# YOTSUBA_GNSS-receiver_MAX_ver_1_0.net
KiCad netlist of a schematic drawn in EAGLE
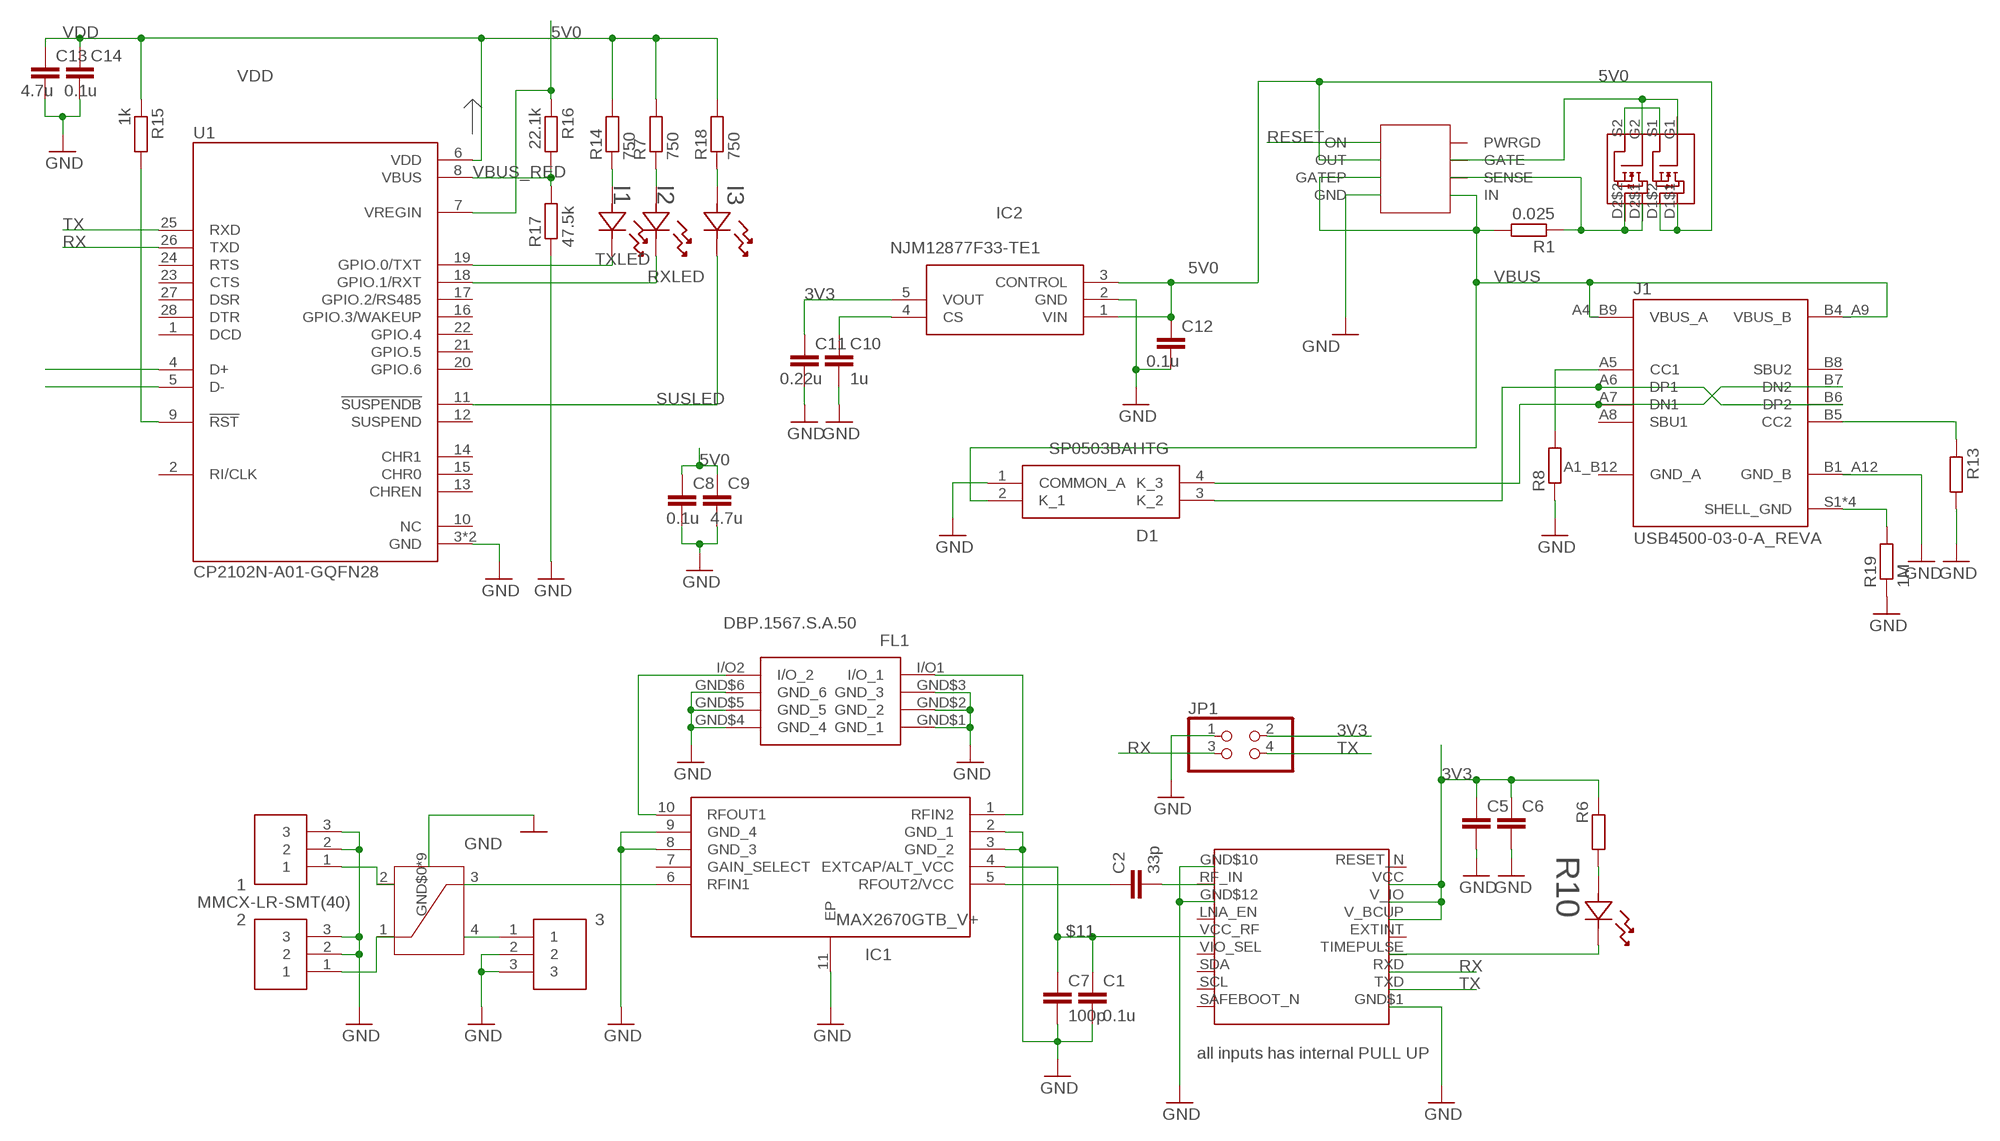
[diagram p0: schematic, sheet 1]

(export (version "E")
  (design (tool "Eeschema 10.0.6"))
  (components
    (comp (ref "1")
      (value "MMCX-LR-SMT(40)")
      (footprint "eagle-import:MMCX-LR-SMT(40)")
      (libsource (lib "eagle-import") (part "MMCX-LR-SMT(40)"))
    )
    (comp (ref "2")
      (value "MMCX-LR-SMT(40)")
      (footprint "eagle-import:MMCX-LR-SMT(40)")
      (libsource (lib "eagle-import") (part "MMCX-LR-SMT(40)"))
    )
    (comp (ref "3")
      (value "MMCX-LR-SMT(40)")
      (footprint "eagle-import:MMCX-LR-SMT(40)")
      (libsource (lib "eagle-import") (part "MMCX-LR-SMT(40)"))
    )
    (comp (ref "C1")
      (value "0.1u")
      (footprint "eagle-import:C1608")
      (libsource (lib "eagle-import") (part "C-EUC1608"))
    )
    (comp (ref "C2")
      (value "33p")
      (footprint "eagle-import:C1608")
      (libsource (lib "eagle-import") (part "C-EUC1608"))
    )
    (comp (ref "C5")
      (value "C-EUC1608")
      (footprint "eagle-import:C1608")
      (libsource (lib "eagle-import") (part "C-EUC1608"))
    )
    (comp (ref "C6")
      (value "C-EUC1608")
      (footprint "eagle-import:C1608")
      (libsource (lib "eagle-import") (part "C-EUC1608"))
    )
    (comp (ref "C7")
      (value "100p")
      (footprint "eagle-import:C1608")
      (libsource (lib "eagle-import") (part "C-EUC1608"))
    )
    (comp (ref "C8")
      (value "0.1u")
      (footprint "eagle-import:C1608")
      (libsource (lib "eagle-import") (part "C-EUC1608"))
    )
    (comp (ref "C9")
      (value "4.7u")
      (footprint "eagle-import:C1608")
      (libsource (lib "eagle-import") (part "C-EUC1608"))
    )
    (comp (ref "C10")
      (value "1u")
      (footprint "eagle-import:C1608")
      (libsource (lib "eagle-import") (part "C-EUC1608"))
    )
    (comp (ref "C11")
      (value "0.22u")
      (footprint "eagle-import:C1608")
      (libsource (lib "eagle-import") (part "C-EUC1608"))
    )
    (comp (ref "C12")
      (value "0.1u")
      (footprint "eagle-import:C1608")
      (libsource (lib "eagle-import") (part "C-EUC1608"))
    )
    (comp (ref "C13")
      (value "4.7u")
      (footprint "eagle-import:C1608")
      (libsource (lib "eagle-import") (part "C-EUC1608"))
    )
    (comp (ref "C14")
      (value "0.1u")
      (footprint "eagle-import:C1608")
      (libsource (lib "eagle-import") (part "C-EUC1608"))
    )
    (comp (ref "D1")
      (value "SP0503BAHTG")
      (footprint "eagle-import:SP0503BAHTG")
      (fields (field (name "MOUSER_PART_NUMBER") "576-SP0503BAHTG"))
      (libsource (lib "eagle-import") (part "SP0503BAHTG"))
    )
    (comp (ref "FL1")
      (value "DBP.1567.S.A.50")
      (footprint "eagle-import:DBP1567SA50")
      (libsource (lib "eagle-import") (part "DBP.1567.S.A.50"))
    )
    (comp (ref "I1")
      (value "SML-E12P8WT86")
      (footprint "eagle-import:LED_SMLD12_ROM")
      (fields (field (name "COPYRIGHT") "Copyright (C) 2023 Ultra Librarian. All rights reserved."))
      (libsource (lib "eagle-import") (part "SML-E12P8WT86"))
    )
    (comp (ref "I2")
      (value "SML-E12P8WT86")
      (footprint "eagle-import:LED_SMLD12_ROM")
      (fields (field (name "COPYRIGHT") "Copyright (C) 2023 Ultra Librarian. All rights reserved."))
      (libsource (lib "eagle-import") (part "SML-E12P8WT86"))
    )
    (comp (ref "I3")
      (value "SML-E12P8WT86")
      (footprint "eagle-import:LED_SMLD12_ROM")
      (fields (field (name "COPYRIGHT") "Copyright (C) 2023 Ultra Librarian. All rights reserved."))
      (libsource (lib "eagle-import") (part "SML-E12P8WT86"))
    )
    (comp (ref "IC1")
      (value "MAX2670GTB_V+")
      (footprint "eagle-import:SON50P300X300X80-11N")
      (fields
        (field (name "MANUFACTURER_PART_NUMBER") "MAX2670GTB/V+")
        (field (name "MOUSER_PART_NUMBER") "700-MAX2670GTB/V+")
      )
      (libsource (lib "eagle-import") (part "MAX2670GTB_V+"))
    )
    (comp (ref "IC2")
      (value "NJM12877F33-TE1")
      (footprint "eagle-import:SOT95P280X120-5N")
      (fields (field (name "MOUSER_PART_NUMBER") "513-NJM12877F33-TE1"))
      (libsource (lib "eagle-import") (part "NJM12877F33-TE1"))
    )
    (comp (ref "J1")
      (value "USB4500-03-0-A_REVA")
      (footprint "eagle-import:GCT_USB4500-03-0-A_REVA")
      (fields
        (field (name "DIGI-KEY_PART_NUMBER") "2073-USB4500-03-0-ATR-ND")
        (field (name "MF") "Global Connector Technology")
        (field (name "MP") "USB4500-03-0-A")
      )
      (libsource (lib "eagle-import") (part "USB4500-03-0-A_REVA"))
    )
    (comp (ref "JP1")
      (value "PINHD-2X2")
      (footprint "eagle-import:2X02")
      (libsource (lib "eagle-import") (part "PINHD-2X2"))
    )
    (comp (ref "R1")
      (value "0.025")
      (footprint "eagle-import:R0603")
      (libsource (lib "eagle-import") (part "R-EU_R0603"))
    )
    (comp (ref "R6")
      (value "R-EU_R0603")
      (footprint "eagle-import:R0603")
      (libsource (lib "eagle-import") (part "R-EU_R0603"))
    )
    (comp (ref "R7")
      (value "750")
      (footprint "eagle-import:R0603")
      (libsource (lib "eagle-import") (part "R-EU_R0603"))
    )
    (comp (ref "R8")
      (value "R-EU_R0603")
      (footprint "eagle-import:R0603")
      (libsource (lib "eagle-import") (part "R-EU_R0603"))
    )
    (comp (ref "R10")
      (value "SML-E12P8WT86")
      (footprint "eagle-import:LED_SMLD12_ROM")
      (fields (field (name "COPYRIGHT") "Copyright (C) 2023 Ultra Librarian. All rights reserved."))
      (libsource (lib "eagle-import") (part "SML-E12P8WT86"))
    )
    (comp (ref "R13")
      (value "R-EU_R0603")
      (footprint "eagle-import:R0603")
      (libsource (lib "eagle-import") (part "R-EU_R0603"))
    )
    (comp (ref "R14")
      (value "750")
      (footprint "eagle-import:R0603")
      (libsource (lib "eagle-import") (part "R-EU_R0603"))
    )
    (comp (ref "R15")
      (value "1k")
      (footprint "eagle-import:R0603")
      (libsource (lib "eagle-import") (part "R-EU_R0603"))
    )
    (comp (ref "R16")
      (value "22.1k")
      (footprint "eagle-import:R0603")
      (libsource (lib "eagle-import") (part "R-EU_R0603"))
    )
    (comp (ref "R17")
      (value "47.5k")
      (footprint "eagle-import:R0603")
      (libsource (lib "eagle-import") (part "R-EU_R0603"))
    )
    (comp (ref "R18")
      (value "750")
      (footprint "eagle-import:R0603")
      (libsource (lib "eagle-import") (part "R-EU_R0603"))
    )
    (comp (ref "R19")
      (value "1M")
      (footprint "eagle-import:R0603")
      (libsource (lib "eagle-import") (part "R-EU_R0603"))
    )
    (comp (ref "U$1")
      (value "MAX_M10S")
      (footprint "eagle-import:MAX-M10S")
      (libsource (lib "eagle-import") (part "MAX_M10S"))
    )
    (comp (ref "U$3")
      (value "HC125.A")
      (footprint "eagle-import:HC125.A")
      (libsource (lib "eagle-import") (part "HC125.A"))
    )
    (comp (ref "U$7")
      (value "DMG6898LSD")
      (footprint "eagle-import:SOIC127P600X150-8N")
      (libsource (lib "eagle-import") (part "DMG6898LSD"))
    )
    (comp (ref "U$8")
      (value "LTC4361")
      (footprint "eagle-import:SOP65P280X100-8N")
      (libsource (lib "eagle-import") (part "LTC4361"))
    )
    (comp (ref "U1")
      (value "CP2102N-A01-GQFN28")
      (footprint "eagle-import:QFN50P500X500X80-29N")
      (fields (field (name "MF") "Silicon Labs"))
      (libsource (lib "eagle-import") (part "CP2102N-A01-GQFN28"))
    )
  )
  (nets
    (net (code "1") (name "/$11") (class "Default")
      (node (ref "C1") (pin "1") (pinfunction "1_1") (pintype "passive"))
      (node (ref "C7") (pin "1") (pinfunction "1_1") (pintype "passive"))
      (node (ref "IC1") (pin "4") (pinfunction "EXTCAP/ALT_VCC_4") (pintype "bidirectional"))
      (node (ref "U$1") (pin "VCC_RF") (pinfunction "VCC_RF_VCC_RF") (pintype "bidirectional"))
    )
    (net (code "2") (name "/3V3") (class "Default")
      (node (ref "C11") (pin "1") (pinfunction "1_1") (pintype "passive"))
      (node (ref "C5") (pin "1") (pinfunction "1_1") (pintype "passive"))
      (node (ref "C6") (pin "1") (pinfunction "1_1") (pintype "passive"))
      (node (ref "IC2") (pin "5") (pinfunction "VOUT_5") (pintype "bidirectional"))
      (node (ref "JP1") (pin "2") (pinfunction "2_2") (pintype "passive"))
      (node (ref "R6") (pin "2") (pinfunction "2_2") (pintype "passive"))
      (node (ref "U$1") (pin "VCC") (pinfunction "VCC_VCC") (pintype "bidirectional"))
      (node (ref "U$1") (pin "V_BCUP") (pinfunction "V_BCKP_V_BCUP") (pintype "bidirectional"))
      (node (ref "U$1") (pin "V_IO") (pinfunction "V_IO_V_IO") (pintype "bidirectional"))
    )
    (net (code "3") (name "/5V0") (class "Default")
      (node (ref "C12") (pin "1") (pinfunction "1_1") (pintype "passive"))
      (node (ref "C8") (pin "1") (pinfunction "1_1") (pintype "passive"))
      (node (ref "C9") (pin "1") (pinfunction "1_1") (pintype "passive"))
      (node (ref "IC2") (pin "1") (pinfunction "VIN_1") (pintype "bidirectional"))
      (node (ref "IC2") (pin "3") (pinfunction "CONTROL_3") (pintype "bidirectional"))
      (node (ref "R16") (pin "1") (pinfunction "1_1") (pintype "passive"))
      (node (ref "U$7") (pin "D1$1") (pinfunction "D1$1_D1$1") (pintype "bidirectional"))
      (node (ref "U$7") (pin "D1$2") (pinfunction "D1$2_D1$2") (pintype "bidirectional"))
      (node (ref "U$8") (pin "OUT") (pinfunction "OUT_OUT") (pintype "bidirectional"))
      (node (ref "U1") (pin "7") (pinfunction "VREGIN_7") (pintype "power_in"))
    )
    (net (code "4") (name "/D+") (class "Default")
      (node (ref "D1") (pin "3") (pinfunction "K_2_3") (pintype "bidirectional"))
      (node (ref "J1") (pin "A6") (pinfunction "DP1_A6") (pintype "bidirectional"))
      (node (ref "J1") (pin "B6") (pinfunction "DP2_B6") (pintype "bidirectional"))
      (node (ref "U1") (pin "4") (pinfunction "D+_4") (pintype "bidirectional"))
    )
    (net (code "5") (name "/D-") (class "Default")
      (node (ref "D1") (pin "4") (pinfunction "K_3_4") (pintype "bidirectional"))
      (node (ref "J1") (pin "A7") (pinfunction "DN1_A7") (pintype "bidirectional"))
      (node (ref "J1") (pin "B7") (pinfunction "DN2_B7") (pintype "bidirectional"))
      (node (ref "U1") (pin "5") (pinfunction "D-_5") (pintype "bidirectional"))
    )
    (net (code "6") (name "/GND_A") (class "Default")
      (node (ref "J1") (pin "A1_B12") (pinfunction "GND_A_A1_B12") (pintype "power_in"))
    )
    (net (code "7") (name "/RESET") (class "Default")
      (node (ref "U$8") (pin "ON") (pinfunction "ON_ON") (pintype "bidirectional"))
    )
    (net (code "8") (name "/RX") (class "Default")
      (node (ref "JP1") (pin "3") (pinfunction "3_3") (pintype "passive"))
      (node (ref "U$1") (pin "RXD") (pinfunction "RXD_RXD") (pintype "bidirectional"))
      (node (ref "U1") (pin "26") (pinfunction "TXD_26") (pintype "output"))
    )
    (net (code "9") (name "/RXLED") (class "Default")
      (node (ref "I2") (pin "1") (pinfunction "1_1") (pintype "passive"))
      (node (ref "U1") (pin "18") (pinfunction "GPIO.1/RXT_18") (pintype "bidirectional"))
    )
    (net (code "10") (name "/SUSLED") (class "Default")
      (node (ref "I3") (pin "1") (pinfunction "1_1") (pintype "passive"))
      (node (ref "U1") (pin "11") (pinfunction "~{SUSPENDB}_11") (pintype "output"))
    )
    (net (code "11") (name "/TX") (class "Default")
      (node (ref "JP1") (pin "4") (pinfunction "4_4") (pintype "passive"))
      (node (ref "U$1") (pin "TXD") (pinfunction "TXD_TXD") (pintype "bidirectional"))
      (node (ref "U1") (pin "25") (pinfunction "RXD_25") (pintype "input"))
    )
    (net (code "12") (name "/TXLED") (class "Default")
      (node (ref "I1") (pin "1") (pinfunction "1_1") (pintype "passive"))
      (node (ref "U1") (pin "19") (pinfunction "GPIO.0/TXT_19") (pintype "bidirectional"))
    )
    (net (code "13") (name "/VBUS") (class "Default")
      (node (ref "D1") (pin "2") (pinfunction "K_1_2") (pintype "bidirectional"))
      (node (ref "J1") (pin "A4_B9") (pinfunction "VBUS_A_A4_B9") (pintype "power_in"))
      (node (ref "J1") (pin "B4_A9") (pinfunction "VBUS_B_B4_A9") (pintype "power_in"))
      (node (ref "R1") (pin "2") (pinfunction "2_2") (pintype "passive"))
      (node (ref "U$8") (pin "GATEP") (pinfunction "GATEP_GATEP") (pintype "bidirectional"))
      (node (ref "U$8") (pin "IN") (pinfunction "IN_IN") (pintype "bidirectional"))
    )
    (net (code "14") (name "/VBUS_RED") (class "Default")
      (node (ref "R16") (pin "2") (pinfunction "2_2") (pintype "passive"))
      (node (ref "R17") (pin "2") (pinfunction "2_2") (pintype "passive"))
      (node (ref "U1") (pin "8") (pinfunction "VBUS_8") (pintype "power_in"))
    )
    (net (code "15") (name "/VDD") (class "Default")
      (node (ref "C13") (pin "1") (pinfunction "1_1") (pintype "passive"))
      (node (ref "C14") (pin "1") (pinfunction "1_1") (pintype "passive"))
      (node (ref "R14") (pin "2") (pinfunction "2_2") (pintype "passive"))
      (node (ref "R15") (pin "1") (pinfunction "1_1") (pintype "passive"))
      (node (ref "R18") (pin "2") (pinfunction "2_2") (pintype "passive"))
      (node (ref "R7") (pin "2") (pinfunction "2_2") (pintype "passive"))
      (node (ref "U1") (pin "6") (pinfunction "VDD_6") (pintype "power_in"))
    )
    (net (code "16") (name "GND") (class "Default")
      (node (ref "1") (pin "2") (pinfunction "2_2") (pintype "bidirectional"))
      (node (ref "1") (pin "3") (pinfunction "3_3") (pintype "bidirectional"))
      (node (ref "2") (pin "2") (pinfunction "2_2") (pintype "bidirectional"))
      (node (ref "2") (pin "3") (pinfunction "3_3") (pintype "bidirectional"))
      (node (ref "3") (pin "2") (pinfunction "2_2") (pintype "bidirectional"))
      (node (ref "3") (pin "3") (pinfunction "3_3") (pintype "bidirectional"))
      (node (ref "C1") (pin "2") (pinfunction "2_2") (pintype "passive"))
      (node (ref "C10") (pin "2") (pinfunction "2_2") (pintype "passive"))
      (node (ref "C11") (pin "2") (pinfunction "2_2") (pintype "passive"))
      (node (ref "C12") (pin "2") (pinfunction "2_2") (pintype "passive"))
      (node (ref "C13") (pin "2") (pinfunction "2_2") (pintype "passive"))
      (node (ref "C14") (pin "2") (pinfunction "2_2") (pintype "passive"))
      (node (ref "C5") (pin "2") (pinfunction "2_2") (pintype "passive"))
      (node (ref "C6") (pin "2") (pinfunction "2_2") (pintype "passive"))
      (node (ref "C7") (pin "2") (pinfunction "2_2") (pintype "passive"))
      (node (ref "C8") (pin "2") (pinfunction "2_2") (pintype "passive"))
      (node (ref "C9") (pin "2") (pinfunction "2_2") (pintype "passive"))
      (node (ref "D1") (pin "1") (pinfunction "COMMON_A_1") (pintype "bidirectional"))
      (node (ref "FL1") (pin "GND$1") (pinfunction "GND_1_GND$1") (pintype "bidirectional"))
      (node (ref "FL1") (pin "GND$2") (pinfunction "GND_2_GND$2") (pintype "bidirectional"))
      (node (ref "FL1") (pin "GND$3") (pinfunction "GND_3_GND$3") (pintype "bidirectional"))
      (node (ref "FL1") (pin "GND$4") (pinfunction "GND_4_GND$4") (pintype "bidirectional"))
      (node (ref "FL1") (pin "GND$5") (pinfunction "GND_5_GND$5") (pintype "bidirectional"))
      (node (ref "FL1") (pin "GND$6") (pinfunction "GND_6_GND$6") (pintype "bidirectional"))
      (node (ref "IC1") (pin "11") (pinfunction "EP_11") (pintype "bidirectional"))
      (node (ref "IC1") (pin "2") (pinfunction "GND_1_2") (pintype "bidirectional"))
      (node (ref "IC1") (pin "3") (pinfunction "GND_2_3") (pintype "bidirectional"))
      (node (ref "IC1") (pin "8") (pinfunction "GND_3_8") (pintype "bidirectional"))
      (node (ref "IC1") (pin "9") (pinfunction "GND_4_9") (pintype "bidirectional"))
      (node (ref "IC2") (pin "2") (pinfunction "GND_2") (pintype "bidirectional"))
      (node (ref "J1") (pin "B1_A12") (pinfunction "GND_B_B1_A12") (pintype "power_in"))
      (node (ref "JP1") (pin "1") (pinfunction "1_1") (pintype "passive"))
      (node (ref "R13") (pin "2") (pinfunction "2_2") (pintype "passive"))
      (node (ref "R17") (pin "1") (pinfunction "1_1") (pintype "passive"))
      (node (ref "R19") (pin "1") (pinfunction "1_1") (pintype "passive"))
      (node (ref "R8") (pin "1") (pinfunction "1_1") (pintype "passive"))
      (node (ref "U$1") (pin "GND$1") (pinfunction "GND$1_GND$1") (pintype "bidirectional"))
      (node (ref "U$1") (pin "GND$10") (pinfunction "GND$10_GND$10") (pintype "bidirectional"))
      (node (ref "U$1") (pin "GND$12") (pinfunction "GND$12_GND$12") (pintype "bidirectional"))
      (node (ref "U$3") (pin "GND$0") (pinfunction "GND_GND$0") (pintype "bidirectional"))
      (node (ref "U$3") (pin "GND$1") (pinfunction "GND_GND$1") (pintype "bidirectional"))
      (node (ref "U$3") (pin "GND$2") (pinfunction "GND_GND$2") (pintype "bidirectional"))
      (node (ref "U$3") (pin "GND$3") (pinfunction "GND_GND$3") (pintype "bidirectional"))
      (node (ref "U$3") (pin "GND$4") (pinfunction "GND_GND$4") (pintype "bidirectional"))
      (node (ref "U$3") (pin "GND$5") (pinfunction "GND_GND$5") (pintype "bidirectional"))
      (node (ref "U$3") (pin "GND$6") (pinfunction "GND_GND$6") (pintype "bidirectional"))
      (node (ref "U$3") (pin "GND$7") (pinfunction "GND_GND$7") (pintype "bidirectional"))
      (node (ref "U$3") (pin "GND$8") (pinfunction "GND_GND$8") (pintype "bidirectional"))
      (node (ref "U$8") (pin "GND") (pinfunction "GND_GND") (pintype "bidirectional"))
      (node (ref "U1") (pin "29") (pinfunction "GND_29") (pintype "power_in"))
      (node (ref "U1") (pin "3") (pinfunction "GND_3") (pintype "power_in"))
    )
    (net (code "17") (name "Net-(1-Pad1)") (class "Default")
      (node (ref "1") (pin "1") (pinfunction "1_1") (pintype "bidirectional"))
      (node (ref "U$3") (pin "2") (pinfunction "2_2") (pintype "bidirectional"))
    )
    (net (code "18") (name "Net-(2-Pad1)") (class "Default")
      (node (ref "2") (pin "1") (pinfunction "1_1") (pintype "bidirectional"))
      (node (ref "U$3") (pin "1") (pinfunction "1_1") (pintype "bidirectional"))
    )
    (net (code "19") (name "Net-(3-Pad1)") (class "Default")
      (node (ref "3") (pin "1") (pinfunction "1_1") (pintype "bidirectional"))
      (node (ref "U$3") (pin "4") (pinfunction "4_4") (pintype "bidirectional"))
    )
    (net (code "20") (name "Net-(C2-Pad2)") (class "Default")
      (node (ref "C2") (pin "2") (pinfunction "2_2") (pintype "passive"))
      (node (ref "U$1") (pin "RF_IN") (pinfunction "RF_IN_RF_IN") (pintype "bidirectional"))
    )
    (net (code "21") (name "Net-(FL1-I{slash}O_1)") (class "Default")
      (node (ref "FL1") (pin "I/O1") (pinfunction "I/O_1_I/O1") (pintype "bidirectional"))
      (node (ref "IC1") (pin "1") (pinfunction "RFIN2_1") (pintype "bidirectional"))
    )
    (net (code "22") (name "Net-(FL1-I{slash}O_2)") (class "Default")
      (node (ref "FL1") (pin "I/O2") (pinfunction "I/O_2_I/O2") (pintype "bidirectional"))
      (node (ref "IC1") (pin "10") (pinfunction "RFOUT1_10") (pintype "bidirectional"))
    )
    (net (code "23") (name "Net-(I1-Pad2)") (class "Default")
      (node (ref "I1") (pin "2") (pinfunction "2_2") (pintype "passive"))
      (node (ref "R14") (pin "1") (pinfunction "1_1") (pintype "passive"))
    )
    (net (code "24") (name "Net-(I2-Pad2)") (class "Default")
      (node (ref "I2") (pin "2") (pinfunction "2_2") (pintype "passive"))
      (node (ref "R7") (pin "1") (pinfunction "1_1") (pintype "passive"))
    )
    (net (code "25") (name "Net-(I3-Pad2)") (class "Default")
      (node (ref "I3") (pin "2") (pinfunction "2_2") (pintype "passive"))
      (node (ref "R18") (pin "1") (pinfunction "1_1") (pintype "passive"))
    )
    (net (code "26") (name "Net-(IC1-RFIN1)") (class "Default")
      (node (ref "IC1") (pin "6") (pinfunction "RFIN1_6") (pintype "bidirectional"))
      (node (ref "U$3") (pin "3") (pinfunction "3_3") (pintype "bidirectional"))
    )
    (net (code "27") (name "Net-(IC1-RFOUT2{slash}VCC)") (class "Default")
      (node (ref "C2") (pin "1") (pinfunction "1_1") (pintype "passive"))
      (node (ref "IC1") (pin "5") (pinfunction "RFOUT2/VCC_5") (pintype "bidirectional"))
    )
    (net (code "28") (name "Net-(IC2-CS)") (class "Default")
      (node (ref "C10") (pin "1") (pinfunction "1_1") (pintype "passive"))
      (node (ref "IC2") (pin "4") (pinfunction "CS_4") (pintype "bidirectional"))
    )
    (net (code "29") (name "Net-(J1-CC1)") (class "Default")
      (node (ref "J1") (pin "A5") (pinfunction "CC1_A5") (pintype "bidirectional"))
      (node (ref "R8") (pin "2") (pinfunction "2_2") (pintype "passive"))
    )
    (net (code "30") (name "Net-(J1-CC2)") (class "Default")
      (node (ref "J1") (pin "B5") (pinfunction "CC2_B5") (pintype "bidirectional"))
      (node (ref "R13") (pin "1") (pinfunction "1_1") (pintype "passive"))
    )
    (net (code "31") (name "Net-(J1-SHELL_GND-PadS1)") (class "Default")
      (node (ref "J1") (pin "S1") (pinfunction "SHELL_GND_S1") (pintype "power_in"))
      (node (ref "J1") (pin "S2") (pinfunction "SHELL_GND_S2") (pintype "power_in"))
      (node (ref "J1") (pin "S3") (pinfunction "SHELL_GND_S3") (pintype "power_in"))
      (node (ref "J1") (pin "S4") (pinfunction "SHELL_GND_S4") (pintype "power_in"))
      (node (ref "R19") (pin "2") (pinfunction "2_2") (pintype "passive"))
    )
    (net (code "32") (name "Net-(R1-Pad1)") (class "Default")
      (node (ref "R1") (pin "1") (pinfunction "1_1") (pintype "passive"))
      (node (ref "U$7") (pin "D2$1") (pinfunction "D2$1_D2$1") (pintype "bidirectional"))
      (node (ref "U$7") (pin "D2$2") (pinfunction "D2$2_D2$2") (pintype "bidirectional"))
      (node (ref "U$8") (pin "SENSE") (pinfunction "SENSE_SENSE") (pintype "bidirectional"))
    )
    (net (code "33") (name "Net-(R10-Pad1)") (class "Default")
      (node (ref "R10") (pin "1") (pinfunction "1_1") (pintype "passive"))
      (node (ref "U$1") (pin "TIMEPULSE") (pinfunction "TIMEPULSE_TIMEPULSE") (pintype "bidirectional"))
    )
    (net (code "34") (name "Net-(R10-Pad2)") (class "Default")
      (node (ref "R10") (pin "2") (pinfunction "2_2") (pintype "passive"))
      (node (ref "R6") (pin "1") (pinfunction "1_1") (pintype "passive"))
    )
    (net (code "35") (name "Net-(U$7-PadG1)") (class "Default")
      (node (ref "U$7") (pin "G1") (pinfunction "G1_G1") (pintype "bidirectional"))
      (node (ref "U$7") (pin "G2") (pinfunction "G2_G2") (pintype "bidirectional"))
      (node (ref "U$8") (pin "GATE") (pinfunction "GATE_GATE") (pintype "bidirectional"))
    )
    (net (code "36") (name "Net-(U$7-PadS1)") (class "Default")
      (node (ref "U$7") (pin "S1") (pinfunction "S1_S1") (pintype "bidirectional"))
      (node (ref "U$7") (pin "S2") (pinfunction "S2_S2") (pintype "bidirectional"))
    )
    (net (code "37") (name "Net-(U1-~{RST})") (class "Default")
      (node (ref "R15") (pin "2") (pinfunction "2_2") (pintype "passive"))
      (node (ref "U1") (pin "9") (pinfunction "~{RST}_9") (pintype "input"))
    )
    (net (code "38") (name "unconnected-(IC1-GAIN_SELECT-Pad7)") (class "Default")
      (node (ref "IC1") (pin "7") (pinfunction "GAIN_SELECT_7") (pintype "bidirectional"))
    )
    (net (code "39") (name "unconnected-(J1-SBU1-PadA8)") (class "Default")
      (node (ref "J1") (pin "A8") (pinfunction "SBU1_A8") (pintype "bidirectional"))
    )
    (net (code "40") (name "unconnected-(J1-SBU2-PadB8)") (class "Default")
      (node (ref "J1") (pin "B8") (pinfunction "SBU2_B8") (pintype "bidirectional"))
    )
    (net (code "41") (name "unconnected-(U$1-PadEXTINT)") (class "Default")
      (node (ref "U$1") (pin "EXTINT") (pinfunction "EXTINT_EXTINT") (pintype "bidirectional"))
    )
    (net (code "42") (name "unconnected-(U$1-PadLNA_EN)") (class "Default")
      (node (ref "U$1") (pin "LNA_EN") (pinfunction "LNA_EN_LNA_EN") (pintype "bidirectional"))
    )
    (net (code "43") (name "unconnected-(U$1-PadRESET_N)") (class "Default")
      (node (ref "U$1") (pin "RESET_N") (pinfunction "RESET_N_RESET_N") (pintype "bidirectional"))
    )
    (net (code "44") (name "unconnected-(U$1-PadSAFEBOOT_N)") (class "Default")
      (node (ref "U$1") (pin "SAFEBOOT_N") (pinfunction "SAFEBOOT_N_SAFEBOOT_N") (pintype "bidirectional"))
    )
    (net (code "45") (name "unconnected-(U$1-PadSCL)") (class "Default")
      (node (ref "U$1") (pin "SCL") (pinfunction "SCL_SCL") (pintype "bidirectional"))
    )
    (net (code "46") (name "unconnected-(U$1-PadSDA)") (class "Default")
      (node (ref "U$1") (pin "SDA") (pinfunction "SDA_SDA") (pintype "bidirectional"))
    )
    (net (code "47") (name "unconnected-(U$1-PadVIO_SEL)") (class "Default")
      (node (ref "U$1") (pin "VIO_SEL") (pinfunction "VIO_SEL_VIO_SEL") (pintype "bidirectional"))
    )
    (net (code "48") (name "unconnected-(U$8-PadPWRGD)") (class "Default")
      (node (ref "U$8") (pin "PWRGD") (pinfunction "PWRGD_PWRGD") (pintype "bidirectional"))
    )
    (net (code "49") (name "unconnected-(U1-CHR0-Pad15)") (class "Default")
      (node (ref "U1") (pin "15") (pinfunction "CHR0_15") (pintype "output"))
    )
    (net (code "50") (name "unconnected-(U1-CHR1-Pad14)") (class "Default")
      (node (ref "U1") (pin "14") (pinfunction "CHR1_14") (pintype "output"))
    )
    (net (code "51") (name "unconnected-(U1-CHREN-Pad13)") (class "Default")
      (node (ref "U1") (pin "13") (pinfunction "CHREN_13") (pintype "output"))
    )
    (net (code "52") (name "unconnected-(U1-CTS-Pad23)") (class "Default")
      (node (ref "U1") (pin "23") (pinfunction "CTS_23") (pintype "input"))
    )
    (net (code "53") (name "unconnected-(U1-DCD-Pad1)") (class "Default")
      (node (ref "U1") (pin "1") (pinfunction "DCD_1") (pintype "input"))
    )
    (net (code "54") (name "unconnected-(U1-DSR-Pad27)") (class "Default")
      (node (ref "U1") (pin "27") (pinfunction "DSR_27") (pintype "input"))
    )
    (net (code "55") (name "unconnected-(U1-DTR-Pad28)") (class "Default")
      (node (ref "U1") (pin "28") (pinfunction "DTR_28") (pintype "output"))
    )
    (net (code "56") (name "unconnected-(U1-GPIO.2{slash}RS485-Pad17)") (class "Default")
      (node (ref "U1") (pin "17") (pinfunction "GPIO.2/RS485_17") (pintype "bidirectional"))
    )
    (net (code "57") (name "unconnected-(U1-GPIO.3{slash}WAKEUP-Pad16)") (class "Default")
      (node (ref "U1") (pin "16") (pinfunction "GPIO.3/WAKEUP_16") (pintype "bidirectional"))
    )
    (net (code "58") (name "unconnected-(U1-GPIO.4-Pad22)") (class "Default")
      (node (ref "U1") (pin "22") (pinfunction "GPIO.4_22") (pintype "bidirectional"))
    )
    (net (code "59") (name "unconnected-(U1-GPIO.5-Pad21)") (class "Default")
      (node (ref "U1") (pin "21") (pinfunction "GPIO.5_21") (pintype "bidirectional"))
    )
    (net (code "60") (name "unconnected-(U1-GPIO.6-Pad20)") (class "Default")
      (node (ref "U1") (pin "20") (pinfunction "GPIO.6_20") (pintype "bidirectional"))
    )
    (net (code "61") (name "unconnected-(U1-NC-Pad10)") (class "Default")
      (node (ref "U1") (pin "10") (pinfunction "NC_10") (pintype "no_connect"))
    )
    (net (code "62") (name "unconnected-(U1-RI{slash}CLK-Pad2)") (class "Default")
      (node (ref "U1") (pin "2") (pinfunction "RI/CLK_2") (pintype "bidirectional"))
    )
    (net (code "63") (name "unconnected-(U1-RTS-Pad24)") (class "Default")
      (node (ref "U1") (pin "24") (pinfunction "RTS_24") (pintype "output"))
    )
    (net (code "64") (name "unconnected-(U1-SUSPEND-Pad12)") (class "Default")
      (node (ref "U1") (pin "12") (pinfunction "SUSPEND_12") (pintype "output"))
    )
  )
)
